# 50VBoost.net
KiCad netlist of a schematic drawn in Altium Designer
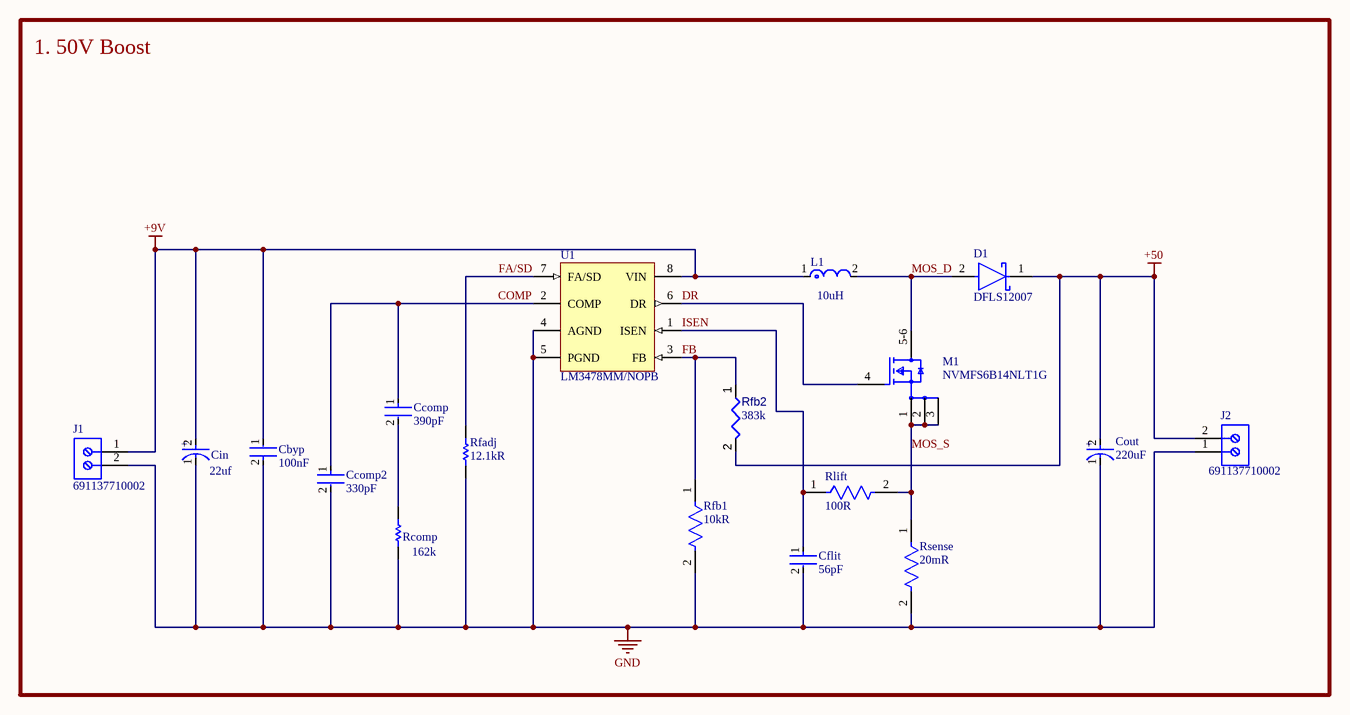
[diagram p0: 50VBoost.SchDoc]

(export (version "E")
  (design (tool "Eeschema 10.0.6"))
  (components
    (comp (ref "Cbyp")
      (value "100nF")
      (footprint "FP-GRM15-MFG")
      (description "Multilayer Ceramic Capacitor, 0.1 uF, 16 V, ± 10%, X7R, 0402 [1005 Metric]")
      (fields (field (name "VOLTAGE") "16V") (field (name "TOLERANCE") "10%"))
      (libsource (lib "SUBC") (part "236180d848d6139a670b325ea6854c9"))
    )
    (comp (ref "Ccomp")
      (value "390pF")
      (footprint "FP-GRM033-0_03-MFG")
      (description "Cap Ceramic 390pF 16V X7R 10% SMD 0201 125°C Paper T/R")
      (fields (field (name "TOLERANCE") "10%") (field (name "Comment") "GRM033R71C391KA01D"))
      (libsource (lib "SUBC") (part "b4654b650e69147ec39a6b967a45e02"))
    )
    (comp (ref "Ccomp2")
      (value "330pF")
      (footprint "FP-CGA1A-0_1-0_03-MFG")
      (description "Cap Ceramic 330pF 50V X7R 10% Pad SMD 0201 125C Automotive T/R")
      (fields (field (name "TOLERANCE") "10%") (field (name "Comment") "CGA1A2X7R1H331K030BA"))
      (libsource (lib "SUBC") (part "b4654b650e69147ec39a6b967a45e02"))
    )
    (comp (ref "Cflit")
      (value "56pF")
      (footprint "FP-CL02-IPC_A")
      (description "Cap Ceramic 56pF 6.3V C0G 5% SMD 01005 125°C Cardboard T/R")
      (fields (field (name "TOLERANCE") "5%") (field (name "Comment") "CL02C560JQ2ANNC"))
      (libsource (lib "SUBC") (part "b4654b650e69147ec39a6b967a45e02"))
    )
    (comp (ref "Cin")
      (value "22uf")
      (footprint "FP-POSCAP-B2-MFG")
      (description "Cap Tant Solid 22uF 20V B2 CASE 20% (3.5 X 2.8 X 1.9mm) SMD 3528 0.09 Ohm 105 C Embossed T/R")
      (libsource (lib "SUBC") (part "cf48714ba7e38822c1575c7ec0b6d1f"))
    )
    (comp (ref "Cout")
      (value "220uF")
      (footprint "FP-FKK16-MFG")
      (description "Aluminum Electrolytic Capacitor, Polarized, Aluminum (wet), 35V, 20% +Tol, 20% -Tol, 100uF")
      (fields (field (name "VOLTAGE") "100V") (field (name "TOLERANCE") "20%"))
      (libsource (lib "SUBC") (part "203bc49f2ac43e59fd269a8c329ed05"))
    )
    (comp (ref "D1")
      (value "DFLS12007")
      (footprint "FP-PowerDI123-MFG")
      (description "Rectifier Diode, Schottky, 1 Phase, 1 Element, 1A, 200V V(RRM), Silicon")
      (libsource (lib "SUBC") (part "1d6ec82d83fb6aee721767c19dac4b9"))
    )
    (comp (ref "J1")
      (value "691137710002")
      (footprint "691137710002")
      (description "Series 1377 - 5.00 mm Horizontal Entry with Pressure Clamp WR-TBL, 2 pin")
      (fields (field (name "VOLTAGE") "300V"))
      (libsource (lib "SUBC") (part "TBL - 1R - 02P - Screw"))
    )
    (comp (ref "J2")
      (value "691137710002")
      (footprint "691137710002")
      (description "Series 1377 - 5.00 mm Horizontal Entry with Pressure Clamp WR-TBL, 2 pin")
      (fields (field (name "VOLTAGE") "300V"))
      (libsource (lib "SUBC") (part "TBL - 1R - 02P - Screw"))
    )
    (comp (ref "L1")
      (value "10uH")
      (footprint "FP-XAL6060-MFG")
      (description "Power inductor, shielded, 20% tol, SMT, RoHS, halogen f")
      (fields (field (name "TOLERANCE") "20%") (field (name "Comment") "XAL6060-103MEB"))
      (libsource (lib "SUBC") (part "4cc4b267dca4c8e51f7102f422741d8"))
    )
    (comp (ref "M1")
      (value "NVMFS6B14NLT1G")
      (footprint "FP-488AA-MFG")
      (description "Single N-Channel Power MOSFET 100V, 55A, 13mΩ")
      (libsource (lib "SUBC") (part "b2a10f8ee8c65efc23df9c1f3151959"))
    )
    (comp (ref "Rcomp")
      (value "162k")
      (footprint "RESC0603X26X15NL03T05")
      (description "Res, Thick Film, 162K, 1%, 0.05W, 0201")
      (libsource (lib "SUBC") (part "RES"))
    )
    (comp (ref "Rfadj")
      (value "12.1kR")
      (footprint "RESC0603X26X15NL03T05")
      (description "Res Thick Film 0201 12.1K Ohm 1% 1/20W ±200ppm/°C Molded SMD Pressed Carrier T/R")
      (fields (field (name "TOLERANCE") "1%") (field (name "Comment") "ERJ-1GEF1212C"))
      (libsource (lib "SUBC") (part "RES"))
    )
    (comp (ref "Rfb1")
      (value "10kR")
      (footprint "FP-ERJ1G-MFG")
      (description "SMD Chip Resistor, 10 kOhm, ± 1%, 50 mW, 0201 [0603 Metric], Thick Film, General Purpose")
      (fields (field (name "TOLERANCE") "1%") (field (name "Comment") "ERJ-1GNF1002C"))
      (libsource (lib "SUBC") (part "1029c3af85768c4190bb7ad29bc67b5"))
    )
    (comp (ref "Rfb2")
      (value "383k")
      (footprint "RESC0402(1005)_L")
      (description "Chip Resistor, 383 kOhms, +/-1 %, 63 mW, -55 to 155 degC, 0402")
      (fields (field (name "TOLERANCE") "1%") (field (name "POWER") "63mW"))
      (libsource (lib "SUBC") (part "RES-2"))
    )
    (comp (ref "Rlift")
      (value "100R")
      (footprint "FP-CRCW0402-e3-IPC_A")
      (description "SMD Chip Resistor, 100 Ohm, ± 1%, 63 mW, 0402 [1005 Metric], Thick Film, General Purpose")
      (fields (field (name "TOLERANCE") "1%") (field (name "Comment") "CRCW0402100RFKED"))
      (libsource (lib "SUBC") (part "1029c3af85768c4190bb7ad29bc67b5"))
    )
    (comp (ref "Rsense")
      (value "20mR")
      (footprint "FP-CSR1206-IPC_A")
      (description "Res Thick Film 1206 0.02 Ohm 1% 1/2W ±100ppm/°C Molded SMD SMD Paper T/R")
      (fields (field (name "TOLERANCE") "1%") (field (name "Comment") "CSR1206FK20L0"))
      (libsource (lib "SUBC") (part "1029c3af85768c4190bb7ad29bc67b5"))
    )
    (comp (ref "U1")
      (value "LM3478MM/NOPB")
      (footprint "DGK0008A_M")
      (description "IC REG CTRLR MULT TOP 8VSSOP")
      (libsource (lib "SUBC") (part "PM-SWREG-LM3478-8"))
    )
  )
  (nets
    (net (code "1") (name "+9V") (class "Default")
      (node (ref "Cbyp") (pin "1") (pinfunction "1_1") (pintype "passive"))
      (node (ref "Cin") (pin "2") (pinfunction "A_2") (pintype "passive"))
      (node (ref "J1") (pin "1") (pinfunction "1_1") (pintype "passive"))
      (node (ref "L1") (pin "1") (pinfunction "1_1") (pintype "passive"))
      (node (ref "U1") (pin "8") (pinfunction "VIN_8") (pintype "power_in"))
    )
    (net (code "2") (name "+50") (class "Default")
      (node (ref "Cout") (pin "2") (pinfunction "A_2") (pintype "passive"))
      (node (ref "D1") (pin "1") (pinfunction "C_1") (pintype "passive"))
      (node (ref "J2") (pin "2") (pinfunction "2_2") (pintype "passive"))
      (node (ref "Rfb2") (pin "2") (pinfunction "2_2") (pintype "passive"))
    )
    (net (code "3") (name "/COMP") (class "Default")
      (node (ref "Ccomp") (pin "1") (pinfunction "1_1") (pintype "passive"))
      (node (ref "Ccomp2") (pin "1") (pinfunction "1_1") (pintype "passive"))
      (node (ref "U1") (pin "2") (pinfunction "COMP_2") (pintype "passive"))
    )
    (net (code "4") (name "/DR") (class "Default")
      (node (ref "M1") (pin "4") (pinfunction "G_4") (pintype "passive"))
      (node (ref "U1") (pin "6") (pinfunction "DR_6") (pintype "output"))
    )
    (net (code "5") (name "/FA{slash}SD") (class "Default")
      (node (ref "Rfadj") (pin "1") (pinfunction "1_1") (pintype "passive"))
      (node (ref "U1") (pin "7") (pinfunction "FA/SD_7") (pintype "input"))
    )
    (net (code "6") (name "/FB") (class "Default")
      (node (ref "Rfb1") (pin "1") (pinfunction "1_1") (pintype "passive"))
      (node (ref "Rfb2") (pin "1") (pinfunction "1_1") (pintype "passive"))
      (node (ref "U1") (pin "3") (pinfunction "FB_3") (pintype "input"))
    )
    (net (code "7") (name "/ISEN") (class "Default")
      (node (ref "Cflit") (pin "1") (pinfunction "1_1") (pintype "passive"))
      (node (ref "Rlift") (pin "1") (pinfunction "1_1") (pintype "passive"))
      (node (ref "U1") (pin "1") (pinfunction "ISEN_1") (pintype "input"))
    )
    (net (code "8") (name "/MOS_D") (class "Default")
      (node (ref "D1") (pin "2") (pinfunction "A_2") (pintype "passive"))
      (node (ref "L1") (pin "2") (pinfunction "2_2") (pintype "passive"))
      (node (ref "M1") (pin "5-6") (pinfunction "D_5-6") (pintype "passive"))
    )
    (net (code "9") (name "/MOS_S") (class "Default")
      (node (ref "M1") (pin "1") (pinfunction "S_1") (pintype "passive"))
      (node (ref "M1") (pin "2") (pinfunction "S_2") (pintype "passive"))
      (node (ref "M1") (pin "3") (pinfunction "S_3") (pintype "passive"))
      (node (ref "Rlift") (pin "2") (pinfunction "2_2") (pintype "passive"))
      (node (ref "Rsense") (pin "1") (pinfunction "1_1") (pintype "passive"))
    )
    (net (code "10") (name "GND") (class "Default")
      (node (ref "Cbyp") (pin "2") (pinfunction "2_2") (pintype "passive"))
      (node (ref "Ccomp2") (pin "2") (pinfunction "2_2") (pintype "passive"))
      (node (ref "Cflit") (pin "2") (pinfunction "2_2") (pintype "passive"))
      (node (ref "Cin") (pin "1") (pinfunction "C_1") (pintype "passive"))
      (node (ref "Cout") (pin "1") (pinfunction "C_1") (pintype "passive"))
      (node (ref "J1") (pin "2") (pinfunction "2_2") (pintype "passive"))
      (node (ref "J2") (pin "1") (pinfunction "1_1") (pintype "passive"))
      (node (ref "Rcomp") (pin "2") (pinfunction "2_2") (pintype "passive"))
      (node (ref "Rfadj") (pin "2") (pinfunction "2_2") (pintype "passive"))
      (node (ref "Rfb1") (pin "2") (pinfunction "2_2") (pintype "passive"))
      (node (ref "Rsense") (pin "2") (pinfunction "2_2") (pintype "passive"))
      (node (ref "U1") (pin "4") (pinfunction "AGND_4") (pintype "power_in"))
      (node (ref "U1") (pin "5") (pinfunction "PGND_5") (pintype "power_in"))
    )
    (net (code "11") (name "Net-(Ccomp-Pad2)") (class "Default")
      (node (ref "Ccomp") (pin "2") (pinfunction "2_2") (pintype "passive"))
      (node (ref "Rcomp") (pin "1") (pinfunction "1_1") (pintype "passive"))
    )
  )
)
